# Grove_-_6-Axis_Accelerometer_Compass_v1_.net
KiCad netlist of a schematic drawn in EAGLE
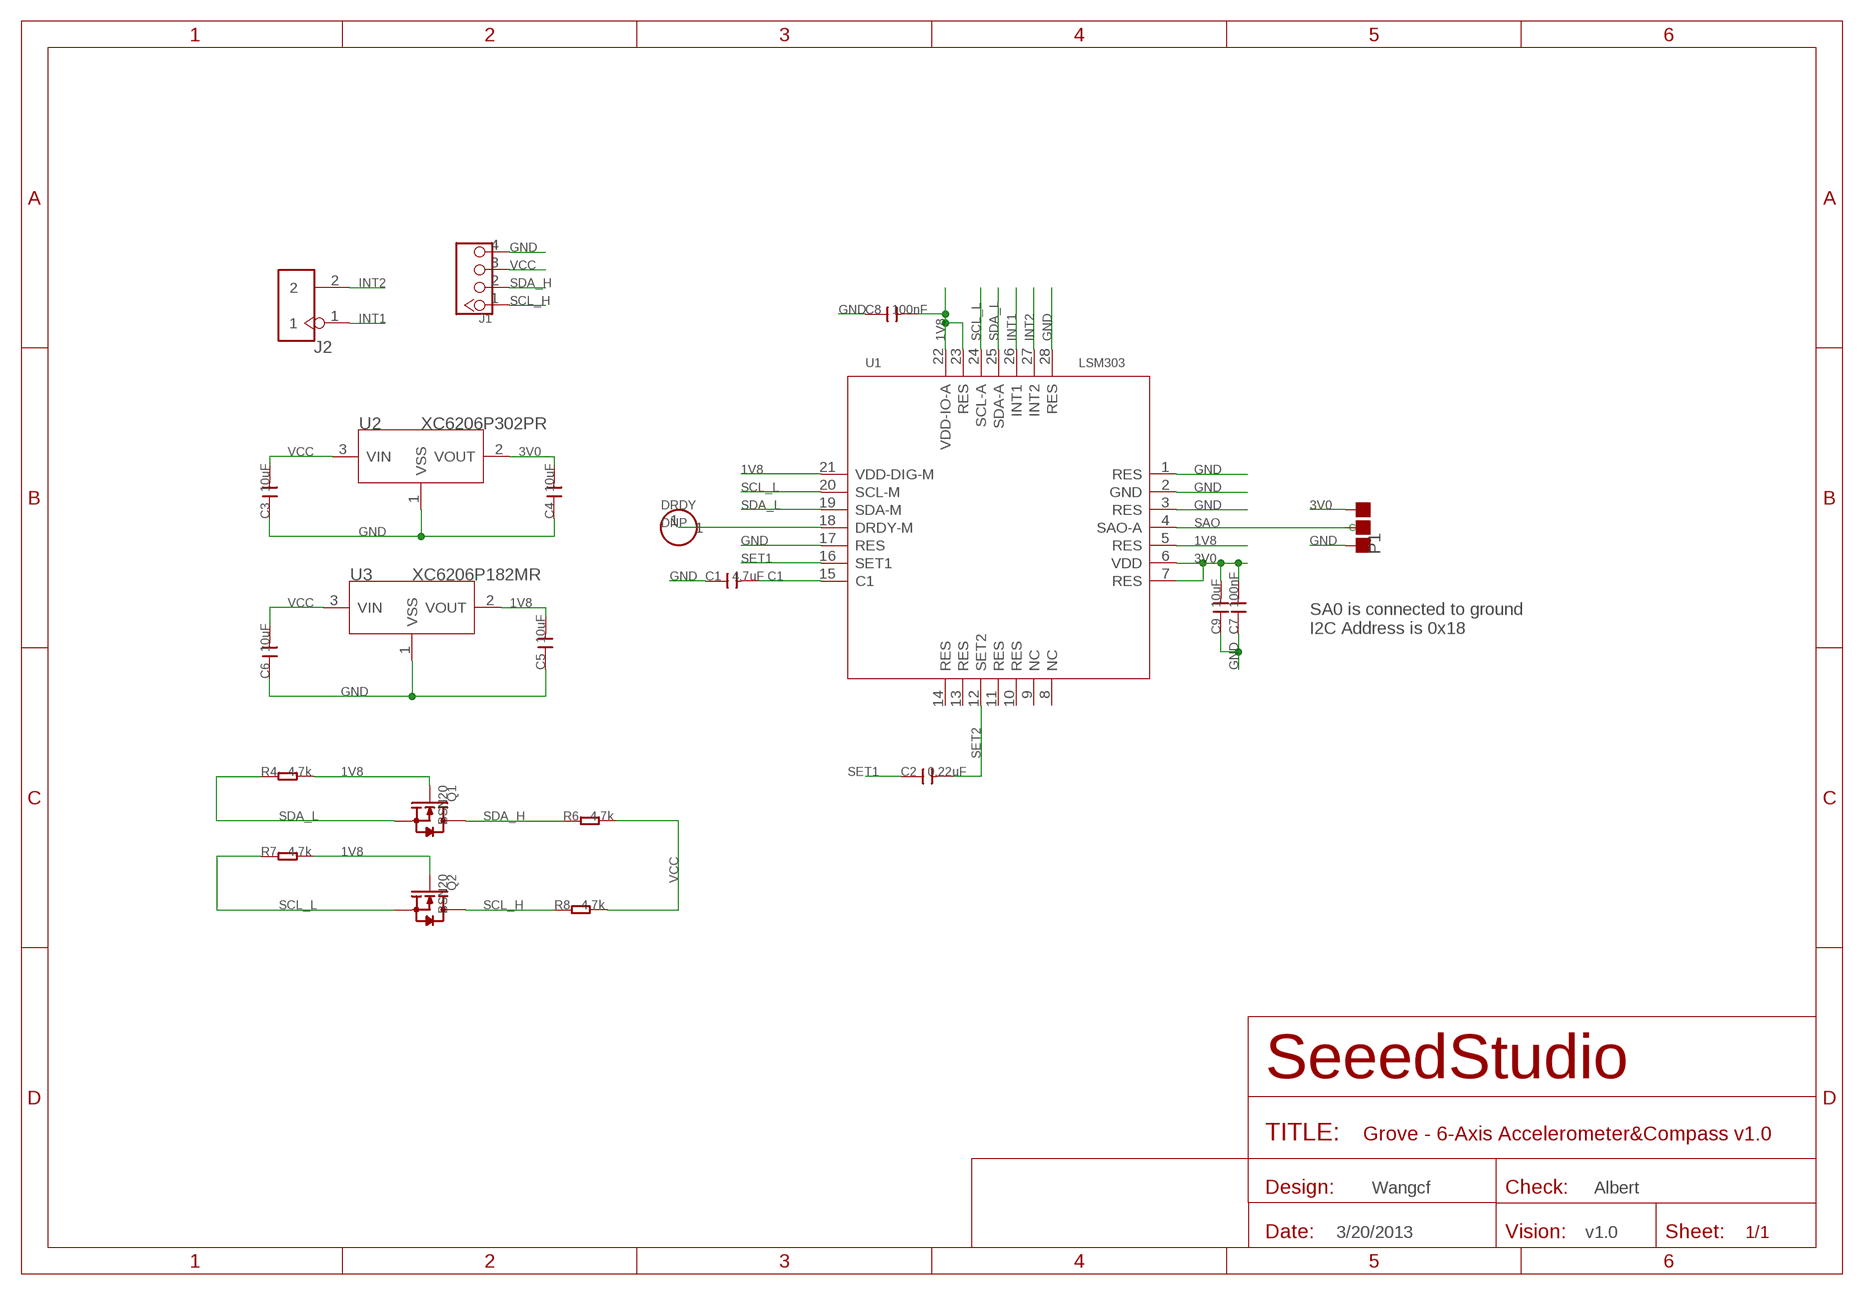
[diagram p0: schematic, sheet 1]

(export (version "E")
  (design (tool "Eeschema 10.0.6"))
  (components
    (comp (ref "C1")
      (value "4.7uF")
      (footprint "eagle-import:C0805")
      (libsource (lib "eagle-import") (part "C-0805"))
    )
    (comp (ref "C2")
      (value "0.22uF")
      (footprint "eagle-import:C0603")
      (libsource (lib "eagle-import") (part "C-0603"))
    )
    (comp (ref "C3")
      (value "10uF")
      (footprint "eagle-import:C0805")
      (libsource (lib "eagle-import") (part "C-0805"))
    )
    (comp (ref "C4")
      (value "10uF")
      (footprint "eagle-import:C0805")
      (libsource (lib "eagle-import") (part "C-0805"))
    )
    (comp (ref "C5")
      (value "10uF")
      (footprint "eagle-import:C0805")
      (libsource (lib "eagle-import") (part "C-0805"))
    )
    (comp (ref "C6")
      (value "10uF")
      (footprint "eagle-import:C0805")
      (libsource (lib "eagle-import") (part "C-0805"))
    )
    (comp (ref "C7")
      (value "100nF")
      (footprint "eagle-import:C0603")
      (libsource (lib "eagle-import") (part "C-0603"))
    )
    (comp (ref "C8")
      (value "100nF")
      (footprint "eagle-import:C0603")
      (libsource (lib "eagle-import") (part "C-0603"))
    )
    (comp (ref "C9")
      (value "10uF")
      (footprint "eagle-import:C0805")
      (libsource (lib "eagle-import") (part "C-0805"))
    )
    (comp (ref "DRDY")
      (value "DNP")
      (footprint "eagle-import:1P-65_35MIL")
      (libsource (lib "eagle-import") (part "HEADER-1P-35"))
    )
    (comp (ref "J1")
      (value "TWIG-4P-2.0-2.0")
      (footprint "eagle-import:4P-2.0")
      (libsource (lib "eagle-import") (part "TWIG-4P-2.0-2.0"))
    )
    (comp (ref "J2")
      (value "HEADER-2P-65/35MIL")
      (footprint "eagle-import:2P-2.54-65_35MIL")
      (libsource (lib "eagle-import") (part "HEADER-2P-65/35MIL"))
    )
    (comp (ref "P1")
      (value "PAD-JUMPER-3P-40*40")
      (footprint "eagle-import:3P-SMD-4.1X1.5")
      (fields (field (name "PARTNO") "DNP"))
      (libsource (lib "eagle-import") (part "PAD-JUMPER-3P-4040"))
    )
    (comp (ref "Q1")
      (value "BSN20")
      (footprint "eagle-import:SOT23")
      (libsource (lib "eagle-import") (part "MOSFET-N'SOT23'"))
    )
    (comp (ref "Q2")
      (value "BSN20")
      (footprint "eagle-import:SOT23")
      (libsource (lib "eagle-import") (part "MOSFET-N'SOT23'"))
    )
    (comp (ref "R4")
      (value "4.7k")
      (footprint "eagle-import:R0603")
      (libsource (lib "eagle-import") (part "R-0603"))
    )
    (comp (ref "R6")
      (value "4.7k")
      (footprint "eagle-import:R0603")
      (libsource (lib "eagle-import") (part "R-0603"))
    )
    (comp (ref "R7")
      (value "4.7k")
      (footprint "eagle-import:R0603")
      (libsource (lib "eagle-import") (part "R-0603"))
    )
    (comp (ref "R8")
      (value "4.7k")
      (footprint "eagle-import:R0603")
      (libsource (lib "eagle-import") (part "R-0603"))
    )
    (comp (ref "U1")
      (value "LSM303")
      (footprint "eagle-import:LGA-28")
      (libsource (lib "eagle-import") (part "LSM303DLH"))
    )
    (comp (ref "U2")
      (value "XC6206P302PR")
      (footprint "eagle-import:SOT23")
      (libsource (lib "eagle-import") (part "XC6206MR"))
    )
    (comp (ref "U3")
      (value "XC6206P182MR")
      (footprint "eagle-import:SOT23")
      (libsource (lib "eagle-import") (part "XC6206MR"))
    )
  )
  (nets
    (net (code "1") (name "/1V8") (class "Default")
      (node (ref "C5") (pin "2") (pinfunction "2_2") (pintype "passive"))
      (node (ref "C8") (pin "2") (pinfunction "2_2") (pintype "passive"))
      (node (ref "Q1") (pin "1") (pinfunction "G_1") (pintype "passive"))
      (node (ref "Q2") (pin "1") (pinfunction "G_1") (pintype "passive"))
      (node (ref "R4") (pin "2") (pinfunction "2_2") (pintype "passive"))
      (node (ref "R7") (pin "2") (pinfunction "2_2") (pintype "passive"))
      (node (ref "U1") (pin "21") (pinfunction "VDD-DIG-M_21") (pintype "bidirectional"))
      (node (ref "U1") (pin "22") (pinfunction "VDD-IO-A_22") (pintype "bidirectional"))
      (node (ref "U1") (pin "23") (pinfunction "RES_23") (pintype "bidirectional"))
      (node (ref "U1") (pin "5") (pinfunction "RES_5") (pintype "bidirectional"))
      (node (ref "U3") (pin "2") (pinfunction "VOUT_2") (pintype "output"))
    )
    (net (code "2") (name "/3V0") (class "Default")
      (node (ref "C4") (pin "2") (pinfunction "2_2") (pintype "passive"))
      (node (ref "C7") (pin "2") (pinfunction "2_2") (pintype "passive"))
      (node (ref "C9") (pin "2") (pinfunction "2_2") (pintype "passive"))
      (node (ref "P1") (pin "00") (pinfunction "L_00") (pintype "bidirectional"))
      (node (ref "U1") (pin "6") (pinfunction "VDD_6") (pintype "bidirectional"))
      (node (ref "U1") (pin "7") (pinfunction "RES_7") (pintype "bidirectional"))
      (node (ref "U2") (pin "2") (pinfunction "VOUT_2") (pintype "output"))
    )
    (net (code "3") (name "/C1") (class "Default")
      (node (ref "C1") (pin "2") (pinfunction "2_2") (pintype "passive"))
      (node (ref "U1") (pin "15") (pinfunction "C1_15") (pintype "bidirectional"))
    )
    (net (code "4") (name "/GND") (class "Default")
      (node (ref "C1") (pin "1") (pinfunction "1_1") (pintype "passive"))
      (node (ref "C3") (pin "1") (pinfunction "1_1") (pintype "passive"))
      (node (ref "C4") (pin "1") (pinfunction "1_1") (pintype "passive"))
      (node (ref "C5") (pin "1") (pinfunction "1_1") (pintype "passive"))
      (node (ref "C6") (pin "1") (pinfunction "1_1") (pintype "passive"))
      (node (ref "C7") (pin "1") (pinfunction "1_1") (pintype "passive"))
      (node (ref "C8") (pin "1") (pinfunction "1_1") (pintype "passive"))
      (node (ref "C9") (pin "1") (pinfunction "1_1") (pintype "passive"))
      (node (ref "J1") (pin "4") (pinfunction "4_4") (pintype "bidirectional"))
      (node (ref "P1") (pin "11") (pinfunction "R_11") (pintype "bidirectional"))
      (node (ref "U1") (pin "1") (pinfunction "RES_1") (pintype "bidirectional"))
      (node (ref "U1") (pin "17") (pinfunction "RES_17") (pintype "bidirectional"))
      (node (ref "U1") (pin "2") (pinfunction "GND_2") (pintype "bidirectional"))
      (node (ref "U1") (pin "28") (pinfunction "RES_28") (pintype "bidirectional"))
      (node (ref "U1") (pin "3") (pinfunction "RES_3") (pintype "bidirectional"))
      (node (ref "U2") (pin "1") (pinfunction "VSS_1") (pintype "power_in"))
      (node (ref "U3") (pin "1") (pinfunction "VSS_1") (pintype "power_in"))
    )
    (net (code "5") (name "/INT1") (class "Default")
      (node (ref "J2") (pin "1") (pinfunction "1_1") (pintype "bidirectional"))
      (node (ref "U1") (pin "26") (pinfunction "INT1_26") (pintype "bidirectional"))
    )
    (net (code "6") (name "/INT2") (class "Default")
      (node (ref "J2") (pin "2") (pinfunction "2_2") (pintype "bidirectional"))
      (node (ref "U1") (pin "27") (pinfunction "INT2_27") (pintype "bidirectional"))
    )
    (net (code "7") (name "/SAO") (class "Default")
      (node (ref "P1") (pin "MM") (pinfunction "C_MM") (pintype "bidirectional"))
      (node (ref "U1") (pin "4") (pinfunction "SAO-A_4") (pintype "bidirectional"))
    )
    (net (code "8") (name "/SCL_H") (class "Default")
      (node (ref "J1") (pin "1") (pinfunction "1_1") (pintype "bidirectional"))
      (node (ref "Q2") (pin "3") (pinfunction "D_3") (pintype "passive"))
      (node (ref "R8") (pin "1") (pinfunction "1_1") (pintype "passive"))
    )
    (net (code "9") (name "/SCL_L") (class "Default")
      (node (ref "Q2") (pin "2") (pinfunction "S_2") (pintype "passive"))
      (node (ref "R7") (pin "1") (pinfunction "1_1") (pintype "passive"))
      (node (ref "U1") (pin "20") (pinfunction "SCL-M_20") (pintype "bidirectional"))
      (node (ref "U1") (pin "24") (pinfunction "SCL-A_24") (pintype "bidirectional"))
    )
    (net (code "10") (name "/SDA_H") (class "Default")
      (node (ref "J1") (pin "2") (pinfunction "2_2") (pintype "bidirectional"))
      (node (ref "Q1") (pin "3") (pinfunction "D_3") (pintype "passive"))
      (node (ref "R6") (pin "1") (pinfunction "1_1") (pintype "passive"))
    )
    (net (code "11") (name "/SDA_L") (class "Default")
      (node (ref "Q1") (pin "2") (pinfunction "S_2") (pintype "passive"))
      (node (ref "R4") (pin "1") (pinfunction "1_1") (pintype "passive"))
      (node (ref "U1") (pin "19") (pinfunction "SDA-M_19") (pintype "bidirectional"))
      (node (ref "U1") (pin "25") (pinfunction "SDA-A_25") (pintype "bidirectional"))
    )
    (net (code "12") (name "/SET1") (class "Default")
      (node (ref "C2") (pin "1") (pinfunction "1_1") (pintype "passive"))
      (node (ref "U1") (pin "16") (pinfunction "SET1_16") (pintype "bidirectional"))
    )
    (net (code "13") (name "/SET2") (class "Default")
      (node (ref "C2") (pin "2") (pinfunction "2_2") (pintype "passive"))
      (node (ref "U1") (pin "12") (pinfunction "SET2_12") (pintype "bidirectional"))
    )
    (net (code "14") (name "/VCC") (class "Default")
      (node (ref "C3") (pin "2") (pinfunction "2_2") (pintype "passive"))
      (node (ref "C6") (pin "2") (pinfunction "2_2") (pintype "passive"))
      (node (ref "J1") (pin "3") (pinfunction "3_3") (pintype "bidirectional"))
      (node (ref "R6") (pin "2") (pinfunction "2_2") (pintype "passive"))
      (node (ref "R8") (pin "2") (pinfunction "2_2") (pintype "passive"))
      (node (ref "U2") (pin "3") (pinfunction "VIN_3") (pintype "input"))
      (node (ref "U3") (pin "3") (pinfunction "VIN_3") (pintype "input"))
    )
    (net (code "15") (name "Net-(U1-DRDY-M)") (class "Default")
      (node (ref "DRDY") (pin "1") (pinfunction "1_1") (pintype "bidirectional"))
      (node (ref "U1") (pin "18") (pinfunction "DRDY-M_18") (pintype "bidirectional"))
    )
    (net (code "16") (name "unconnected-(U1-NC-Pad8)") (class "Default")
      (node (ref "U1") (pin "8") (pinfunction "NC_8") (pintype "bidirectional"))
    )
    (net (code "17") (name "unconnected-(U1-NC-Pad9)") (class "Default")
      (node (ref "U1") (pin "9") (pinfunction "NC_9") (pintype "bidirectional"))
    )
    (net (code "18") (name "unconnected-(U1-RES-Pad10)") (class "Default")
      (node (ref "U1") (pin "10") (pinfunction "RES_10") (pintype "bidirectional"))
    )
    (net (code "19") (name "unconnected-(U1-RES-Pad11)") (class "Default")
      (node (ref "U1") (pin "11") (pinfunction "RES_11") (pintype "bidirectional"))
    )
    (net (code "20") (name "unconnected-(U1-RES-Pad13)") (class "Default")
      (node (ref "U1") (pin "13") (pinfunction "RES_13") (pintype "bidirectional"))
    )
    (net (code "21") (name "unconnected-(U1-RES-Pad14)") (class "Default")
      (node (ref "U1") (pin "14") (pinfunction "RES_14") (pintype "bidirectional"))
    )
  )
)
